# RELAY.net
KiCad netlist of a schematic drawn in Altium Designer
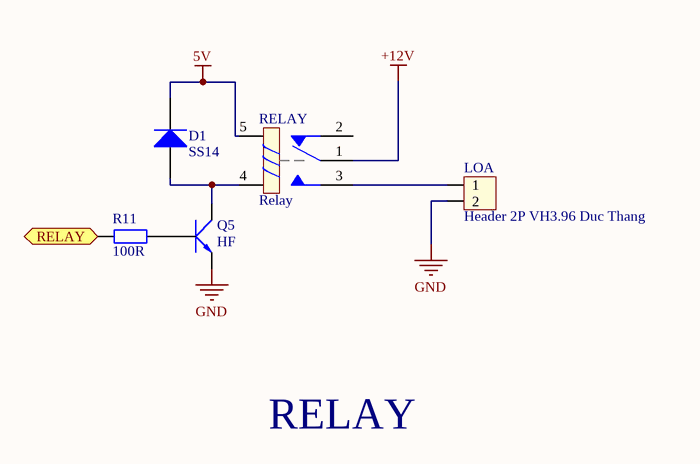
[diagram p0: RELAY.SchDoc]

(export (version "E")
  (design (tool "Eeschema 10.0.6"))
  (components
    (comp (ref "D1")
      (value "SS14")
      (footprint "DIODE SMA")
      (description "Dán")
      (libsource (lib "Altium_Lib_by_KhueNguyenCreator") (part "Diode SS14 ( 1N5819)"))
    )
    (comp (ref "LOA")
      (value "Header 2P VH3.96 Duc Thang")
      (footprint "VH3.96M-2")
      (description "Cắm")
      (libsource (lib "Altium_Lib_by_KhueNguyenCreator") (part "Header 2P VH3.96 Duc Thang"))
    )
    (comp (ref "Q5")
      (value "HF")
      (footprint "SOT23")
      (description "NPN transistor")
      (libsource (lib "Altium_Lib_by_KhueNguyenCreator") (part "C1815 HF SMD"))
    )
    (comp (ref "R11")
      (value "100R")
      (footprint "tro smd 0603")
      (description "Dán")
      (libsource (lib "Altium_Lib_by_KhueNguyenCreator") (part "Tro 0603 5% 100R"))
    )
    (comp (ref "RELAY")
      (value "Relay")
      (footprint "Relay 5 Chan SRD")
      (description "Relay 5 Chan")
      (libsource (lib "Altium_Lib_by_KhueNguyenCreator") (part "Relay 5 Chan SRD"))
    )
  )
  (nets
    (net (code "1") (name "+12V") (class "Default")
      (node (ref "RELAY") (pin "1") (pinfunction "1_1") (pintype "passive"))
    )
    (net (code "2") (name "/RELAY") (class "Default")
      (node (ref "R11") (pin "1") (pinfunction "1_1") (pintype "passive"))
    )
    (net (code "3") (name "5V") (class "Default")
      (node (ref "D1") (pin "2") (pinfunction "K_2") (pintype "passive"))
      (node (ref "RELAY") (pin "5") (pinfunction "5_5") (pintype "passive"))
    )
    (net (code "4") (name "GND") (class "Default")
      (node (ref "LOA") (pin "2") (pinfunction "2_2") (pintype "passive"))
      (node (ref "Q5") (pin "2") (pinfunction "E_2") (pintype "passive"))
    )
    (net (code "5") (name "Net-(D1-A)") (class "Default")
      (node (ref "D1") (pin "1") (pinfunction "A_1") (pintype "passive"))
      (node (ref "Q5") (pin "3") (pinfunction "C_3") (pintype "passive"))
      (node (ref "RELAY") (pin "4") (pinfunction "4_4") (pintype "passive"))
    )
    (net (code "6") (name "Net-(LOA-Pad1)") (class "Default")
      (node (ref "LOA") (pin "1") (pinfunction "1_1") (pintype "passive"))
      (node (ref "RELAY") (pin "3") (pinfunction "3_3") (pintype "passive"))
    )
    (net (code "7") (name "Net-(Q5-B)") (class "Default")
      (node (ref "Q5") (pin "1") (pinfunction "B_1") (pintype "passive"))
      (node (ref "R11") (pin "2") (pinfunction "2_2") (pintype "passive"))
    )
    (net (code "8") (name "unconnected-(RELAY-Pad2)") (class "Default")
      (node (ref "RELAY") (pin "2") (pinfunction "2_2") (pintype "passive"))
    )
  )
)
